# SCH_abi_2024-02-13.net
KiCad netlist of a schematic drawn in EasyEDA
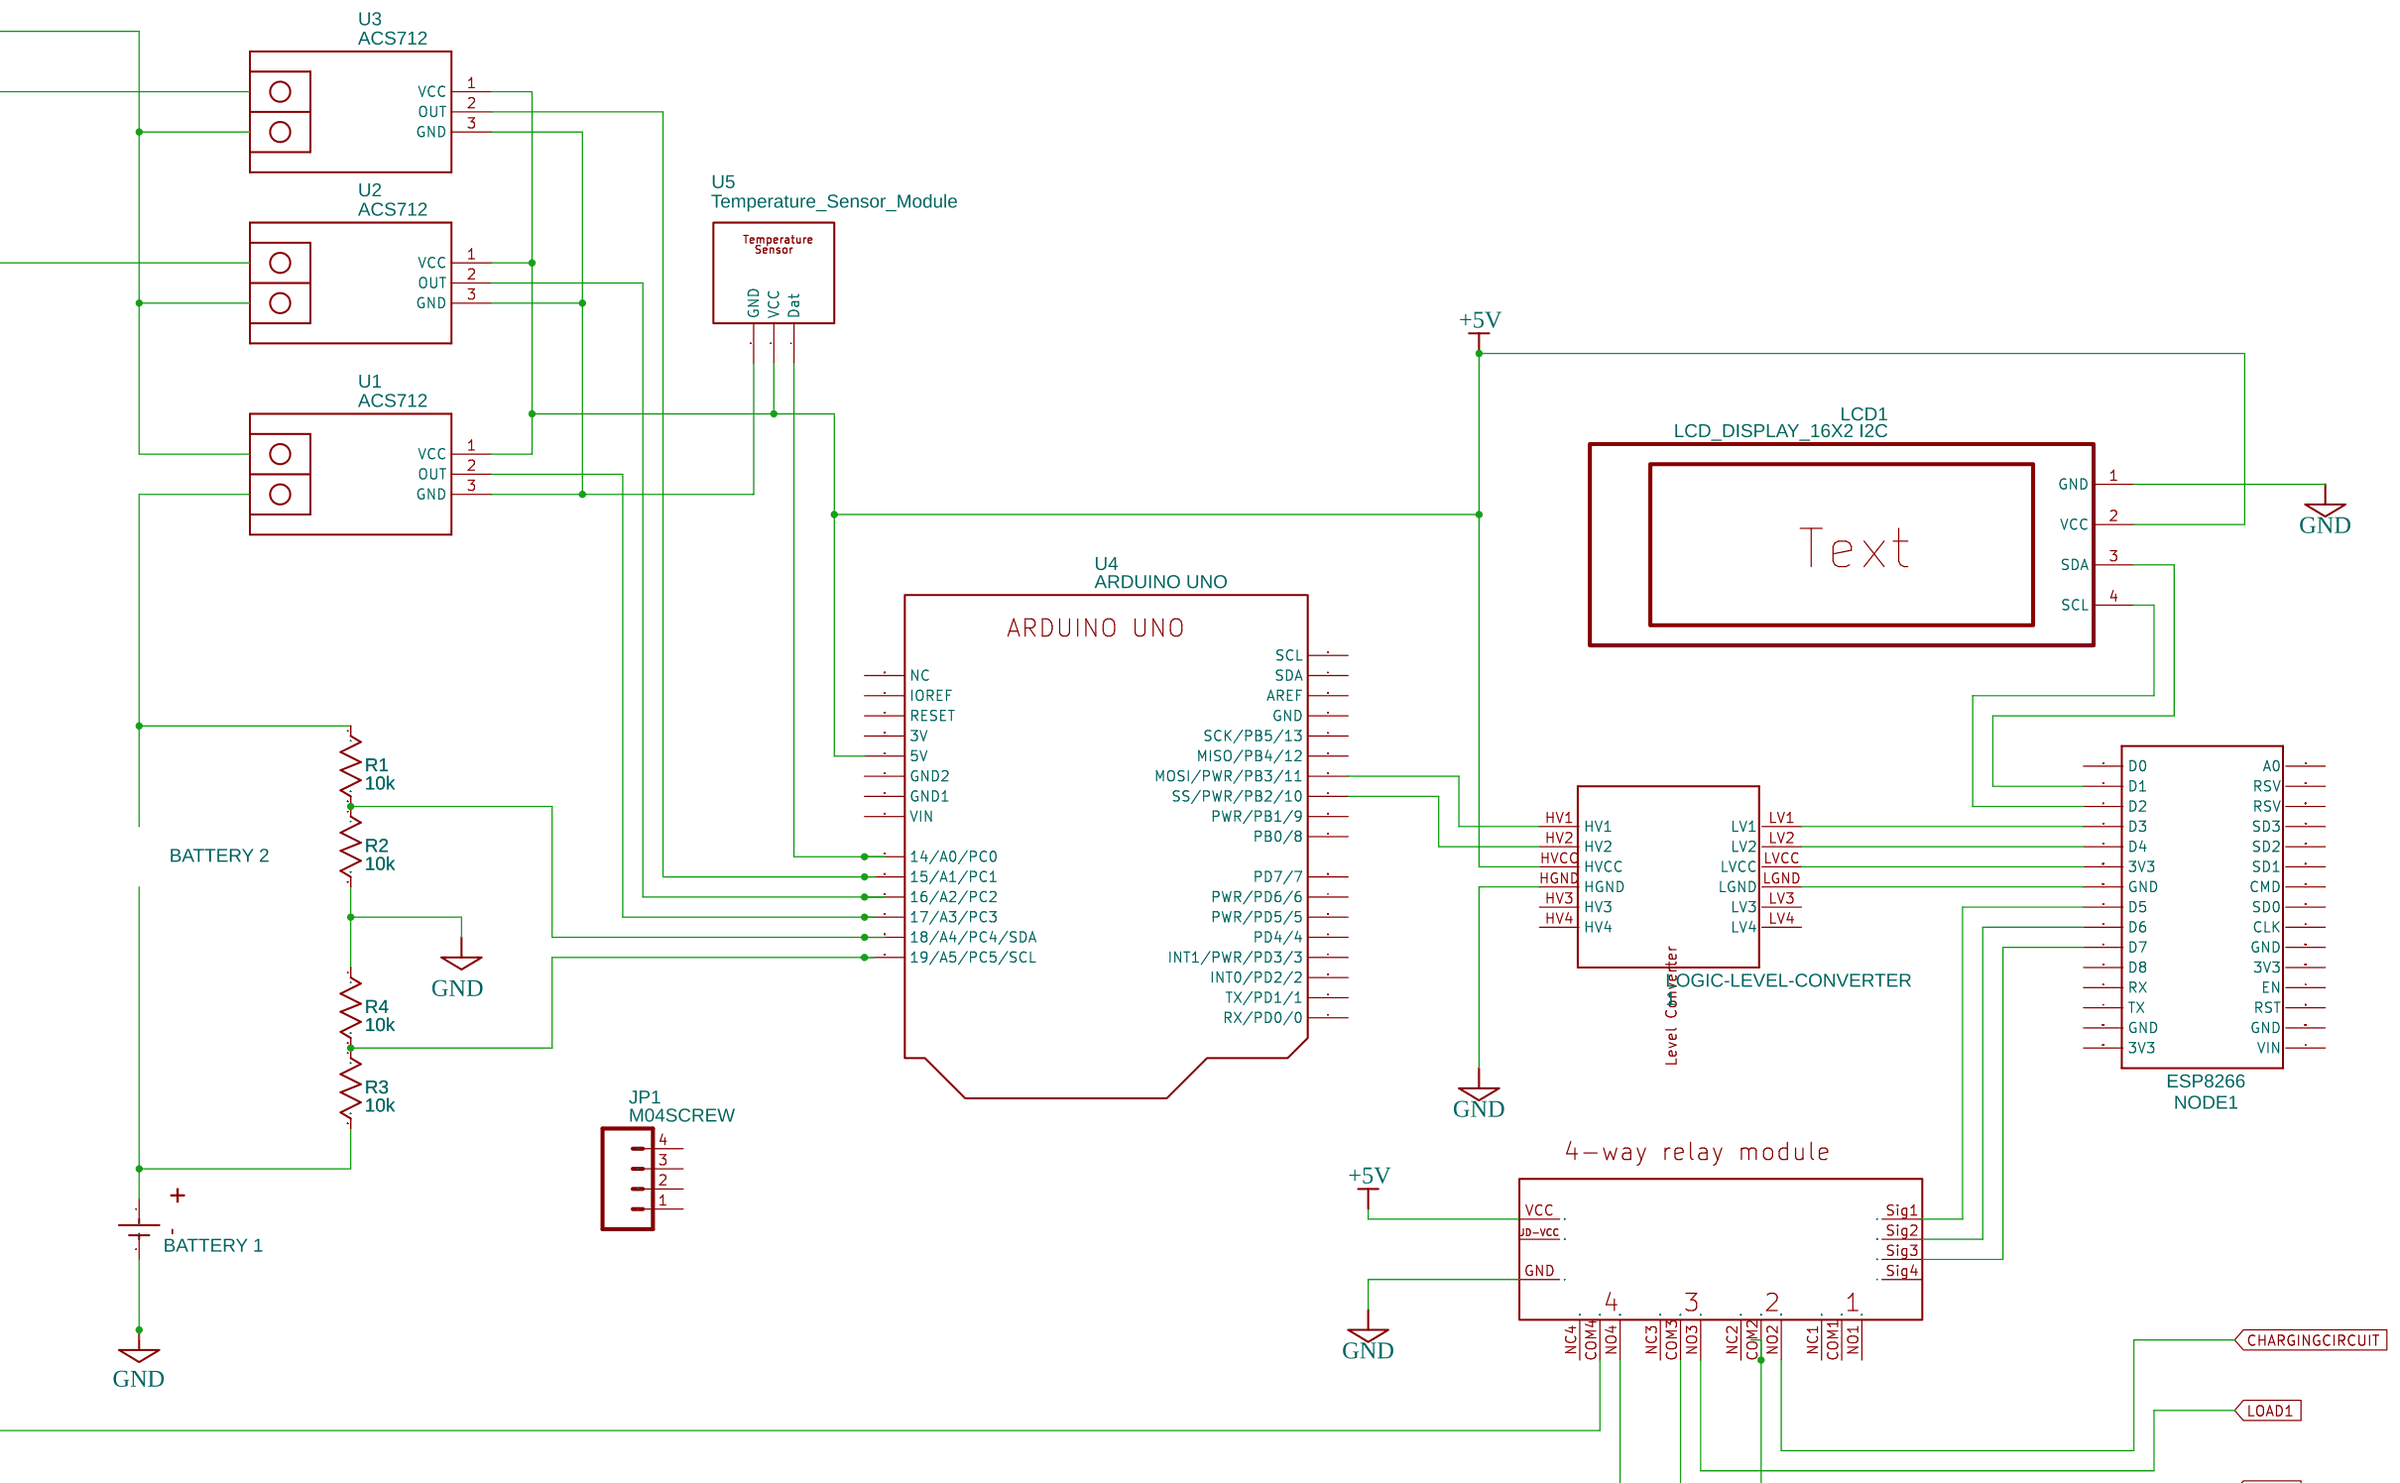
[diagram p0: schematic sheet]

(export (version "E")
  (design (tool "Eeschema 10.0.6"))
  (components
    (comp (ref "1") (value "LOGIC-LEVEL-CONVERTER") (libsource (lib "") (part "LOGIC-LEVEL-CONVERTER")))
    (comp (ref "G2") (value "BATTERY 1") (libsource (lib "") (part "BATTERY-1ELEMENT_RevE_Date15jun2010")))
    (comp (ref "JP1") (value "M04SCREW") (libsource (lib "") (part "M04SCREW")))
    (comp (ref "LCD1") (value "LCD_DISPLAY_16X2 I2C") (libsource (lib "") (part "LCD_DISPLAY_16X2 I2C")))
    (comp (ref "NODE1") (value "ESP8266") (libsource (lib "") (part "ESP8266 COPY")))
    (comp (ref "R1") (value "10k") (libsource (lib "") (part "R_0603_US")))
    (comp (ref "R2") (value "10k") (libsource (lib "") (part "R_0603_US")))
    (comp (ref "R3") (value "10k") (libsource (lib "") (part "R_0603_US")))
    (comp (ref "R4") (value "10k") (libsource (lib "") (part "R_0603_US")))
    (comp (ref "U1") (value "ACS712") (libsource (lib "") (part "CURRENT-SENSOR-ACS712")))
    (comp (ref "U2") (value "ACS712") (libsource (lib "") (part "CURRENT-SENSOR-ACS712")))
    (comp (ref "U3") (value "ACS712") (libsource (lib "") (part "CURRENT-SENSOR-ACS712")))
    (comp (ref "U4") (value "ARDUINO UNO") (libsource (lib "") (part "ARDUINO UNO")))
    (comp (ref "U5")
      (value "Temperature_Sensor_Module")
      (libsource (lib "") (part "DS18B20_Temperature_Sensor_Module"))
    )
    (comp (ref "U6") (value "4 way relay") (libsource (lib "") (part "4 way relay")))
  )
  (nets
    (net (code "1") (name "+5V") (class "Default")
      (node (ref "1") (pin "HVCC") (pinfunction "HVCC_HVCC") (pintype "bidirectional"))
      (node (ref "LCD1") (pin "2") (pinfunction "VCC_2") (pintype "passive"))
      (node (ref "U1") (pin "1") (pinfunction "VCC_1") (pintype "passive"))
      (node (ref "U2") (pin "1") (pinfunction "VCC_1") (pintype "passive"))
      (node (ref "U3") (pin "1") (pinfunction "VCC_1") (pintype "passive"))
      (node (ref "U4") (pin "28") (pinfunction "5V_28") (pintype "passive"))
      (node (ref "U5") (pin "2") (pinfunction "VCC_2") (pintype "unspecified"))
      (node (ref "U6") (pin "VCC") (pinfunction "6_VCC") (pintype "unspecified"))
    )
    (net (code "2") (name "CHARGINGCIRCUIT") (class "Default")
      (node (ref "U6") (pin "NO2") (pinfunction "8_NO2") (pintype "unspecified"))
    )
    (net (code "3") (name "GND") (class "Default")
      (node (ref "1") (pin "HGND") (pinfunction "HGND_HGND") (pintype "bidirectional"))
      (node (ref "G2") (pin "2") (pinfunction "Minus_2") (pintype "bidirectional"))
      (node (ref "LCD1") (pin "1") (pinfunction "GND_1") (pintype "passive"))
      (node (ref "R2") (pin "2") (pinfunction "2_2") (pintype "unspecified"))
      (node (ref "R4") (pin "1") (pinfunction "1_1") (pintype "unspecified"))
      (node (ref "U6") (pin "GND") (pinfunction "5_GND") (pintype "unspecified"))
    )
    (net (code "4") (name "LOAD1") (class "Default")
      (node (ref "U6") (pin "NO3") (pinfunction "8_NO3") (pintype "unspecified"))
    )
    (net (code "5") (name "LOAD2") (class "Default")
      (node (ref "U6") (pin "NO4") (pinfunction "8_NO4") (pintype "unspecified"))
    )
    (net (code "6") (name "Net-(1-PadLGND)") (class "Default")
      (node (ref "1") (pin "LGND") (pinfunction "LGND_LGND") (pintype "bidirectional"))
      (node (ref "NODE1") (pin "GND@2") (pinfunction "GND_GND@2") (pintype "bidirectional"))
    )
    (net (code "7") (name "Net-(1-PadLV1)") (class "Default")
      (node (ref "1") (pin "LV1") (pinfunction "LV1_LV1") (pintype "bidirectional"))
      (node (ref "NODE1") (pin "D3") (pinfunction "D3_D3") (pintype "bidirectional"))
    )
    (net (code "8") (name "Net-(1-PadLV2)") (class "Default")
      (node (ref "1") (pin "LV2") (pinfunction "LV2_LV2") (pintype "bidirectional"))
      (node (ref "NODE1") (pin "D4") (pinfunction "D4_D4") (pintype "bidirectional"))
    )
    (net (code "9") (name "Net-(1-PadLVCC)") (class "Default")
      (node (ref "1") (pin "LVCC") (pinfunction "LVCC_LVCC") (pintype "bidirectional"))
      (node (ref "NODE1") (pin "3V3@2") (pinfunction "3V3_3V3@2") (pintype "bidirectional"))
    )
    (net (code "10") (name "Net-(G2-Plus)") (class "Default")
      (node (ref "G2") (pin "1") (pinfunction "Plus_1") (pintype "bidirectional"))
      (node (ref "R3") (pin "2") (pinfunction "2_2") (pintype "unspecified"))
    )
    (net (code "11") (name "Net-(LCD1-SCL)") (class "Default")
      (node (ref "LCD1") (pin "4") (pinfunction "SCL_4") (pintype "passive"))
      (node (ref "NODE1") (pin "D2") (pinfunction "D2_D2") (pintype "bidirectional"))
    )
    (net (code "12") (name "Net-(LCD1-SDA)") (class "Default")
      (node (ref "LCD1") (pin "3") (pinfunction "SDA_3") (pintype "passive"))
      (node (ref "NODE1") (pin "D1") (pinfunction "D1_D1") (pintype "bidirectional"))
    )
    (net (code "13") (name "Net-(U1-GND)") (class "Default")
      (node (ref "U1") (pin "3") (pinfunction "GND_3") (pintype "passive"))
      (node (ref "U2") (pin "3") (pinfunction "GND_3") (pintype "passive"))
      (node (ref "U3") (pin "3") (pinfunction "GND_3") (pintype "passive"))
      (node (ref "U5") (pin "3") (pinfunction "GND_3") (pintype "unspecified"))
    )
    (net (code "14") (name "Net-(U1-OUT)") (class "Default")
      (node (ref "U1") (pin "2") (pinfunction "OUT_2") (pintype "output"))
      (node (ref "U4") (pin "21") (pinfunction "17/A3/PC3_21") (pintype "unspecified"))
    )
    (net (code "15") (name "Net-(U2-OUT)") (class "Default")
      (node (ref "U2") (pin "2") (pinfunction "OUT_2") (pintype "output"))
      (node (ref "U4") (pin "22") (pinfunction "16/A2/PC2_22") (pintype "unspecified"))
    )
    (net (code "16") (name "Net-(U3-OUT)") (class "Default")
      (node (ref "U3") (pin "2") (pinfunction "OUT_2") (pintype "output"))
      (node (ref "U4") (pin "23") (pinfunction "15/A1/PC1_23") (pintype "unspecified"))
    )
    (net (code "17") (name "Net-(U4-14{slash}A0{slash}PC0)") (class "Default")
      (node (ref "U4") (pin "24") (pinfunction "14/A0/PC0_24") (pintype "unspecified"))
      (node (ref "U5") (pin "1") (pinfunction "Dat_1") (pintype "unspecified"))
    )
    (net (code "18") (name "Net-(U4-18{slash}A4{slash}PC4{slash}SDA)") (class "Default")
      (node (ref "R1") (pin "2") (pinfunction "2_2") (pintype "unspecified"))
      (node (ref "R2") (pin "1") (pinfunction "1_1") (pintype "unspecified"))
      (node (ref "U4") (pin "20") (pinfunction "18/A4/PC4/SDA_20") (pintype "unspecified"))
    )
    (net (code "19") (name "Net-(U4-19{slash}A5{slash}PC5{slash}SCL)") (class "Default")
      (node (ref "R3") (pin "1") (pinfunction "1_1") (pintype "unspecified"))
      (node (ref "R4") (pin "2") (pinfunction "2_2") (pintype "unspecified"))
      (node (ref "U4") (pin "19") (pinfunction "19/A5/PC5/SCL_19") (pintype "unspecified"))
    )
    (net (code "20") (name "Net-(U4-MOSI{slash}PWR{slash}PB3{slash}11)") (class "Default")
      (node (ref "1") (pin "HV1") (pinfunction "HV1_HV1") (pintype "bidirectional"))
      (node (ref "U4") (pin "12") (pinfunction "MOSI/PWR/PB3/11_12") (pintype "unspecified"))
    )
    (net (code "21") (name "Net-(U4-SS{slash}PWR{slash}PB2{slash}10)") (class "Default")
      (node (ref "1") (pin "HV2") (pinfunction "HV2_HV2") (pintype "bidirectional"))
      (node (ref "U4") (pin "11") (pinfunction "SS/PWR/PB2/10_11") (pintype "unspecified"))
    )
    (net (code "22") (name "Net-(U6-1)") (class "Default")
      (node (ref "NODE1") (pin "D5") (pinfunction "D5_D5") (pintype "bidirectional"))
      (node (ref "U6") (pin "Sig1") (pinfunction "1_Sig1") (pintype "unspecified"))
    )
    (net (code "23") (name "Net-(U6-2)") (class "Default")
      (node (ref "NODE1") (pin "D6") (pinfunction "D6_D6") (pintype "bidirectional"))
      (node (ref "U6") (pin "Sig2") (pinfunction "2_Sig2") (pintype "unspecified"))
    )
    (net (code "24") (name "Net-(U6-3)") (class "Default")
      (node (ref "NODE1") (pin "D7") (pinfunction "D7_D7") (pintype "bidirectional"))
      (node (ref "U6") (pin "Sig3") (pinfunction "3_Sig3") (pintype "unspecified"))
    )
    (net (code "25") (name "unconnected-(1-PadHV3)") (class "Default")
      (node (ref "1") (pin "HV3") (pinfunction "HV3_HV3") (pintype "bidirectional"))
    )
    (net (code "26") (name "unconnected-(1-PadHV4)") (class "Default")
      (node (ref "1") (pin "HV4") (pinfunction "HV4_HV4") (pintype "bidirectional"))
    )
    (net (code "27") (name "unconnected-(1-PadLV3)") (class "Default")
      (node (ref "1") (pin "LV3") (pinfunction "LV3_LV3") (pintype "bidirectional"))
    )
    (net (code "28") (name "unconnected-(1-PadLV4)") (class "Default")
      (node (ref "1") (pin "LV4") (pinfunction "LV4_LV4") (pintype "bidirectional"))
    )
    (net (code "29") (name "unconnected-(JP1-Pad1)") (class "Default")
      (node (ref "JP1") (pin "1") (pinfunction "1_1") (pintype "unspecified"))
    )
    (net (code "30") (name "unconnected-(JP1-Pad2)") (class "Default")
      (node (ref "JP1") (pin "2") (pinfunction "2_2") (pintype "unspecified"))
    )
    (net (code "31") (name "unconnected-(JP1-Pad3)") (class "Default")
      (node (ref "JP1") (pin "3") (pinfunction "3_3") (pintype "unspecified"))
    )
    (net (code "32") (name "unconnected-(JP1-Pad4)") (class "Default")
      (node (ref "JP1") (pin "4") (pinfunction "4_4") (pintype "unspecified"))
    )
    (net (code "33") (name "unconnected-(NODE1-3V3-Pad3V3@1)") (class "Default")
      (node (ref "NODE1") (pin "3V3@1") (pinfunction "3V3_3V3@1") (pintype "bidirectional"))
    )
    (net (code "34") (name "unconnected-(NODE1-3V3-Pad3V3@3)") (class "Default")
      (node (ref "NODE1") (pin "3V3@3") (pinfunction "3V3_3V3@3") (pintype "bidirectional"))
    )
    (net (code "35") (name "unconnected-(NODE1-GND-PadGND@1)") (class "Default")
      (node (ref "NODE1") (pin "GND@1") (pinfunction "GND_GND@1") (pintype "bidirectional"))
    )
    (net (code "36") (name "unconnected-(NODE1-GND-PadGND@3)") (class "Default")
      (node (ref "NODE1") (pin "GND@3") (pinfunction "GND_GND@3") (pintype "bidirectional"))
    )
    (net (code "37") (name "unconnected-(NODE1-GND-PadGND@4)") (class "Default")
      (node (ref "NODE1") (pin "GND@4") (pinfunction "GND_GND@4") (pintype "bidirectional"))
    )
    (net (code "38") (name "unconnected-(NODE1-PadA0)") (class "Default")
      (node (ref "NODE1") (pin "A0") (pinfunction "A0_A0") (pintype "bidirectional"))
    )
    (net (code "39") (name "unconnected-(NODE1-PadCLK)") (class "Default")
      (node (ref "NODE1") (pin "CLK") (pinfunction "CLK_CLK") (pintype "bidirectional"))
    )
    (net (code "40") (name "unconnected-(NODE1-PadCMD)") (class "Default")
      (node (ref "NODE1") (pin "CMD") (pinfunction "CMD_CMD") (pintype "bidirectional"))
    )
    (net (code "41") (name "unconnected-(NODE1-PadD0)") (class "Default")
      (node (ref "NODE1") (pin "D0") (pinfunction "D0_D0") (pintype "bidirectional"))
    )
    (net (code "42") (name "unconnected-(NODE1-PadD8)") (class "Default")
      (node (ref "NODE1") (pin "D8") (pinfunction "D8_D8") (pintype "bidirectional"))
    )
    (net (code "43") (name "unconnected-(NODE1-PadEN)") (class "Default")
      (node (ref "NODE1") (pin "EN") (pinfunction "EN_EN") (pintype "bidirectional"))
    )
    (net (code "44") (name "unconnected-(NODE1-PadRST)") (class "Default")
      (node (ref "NODE1") (pin "RST") (pinfunction "RST_RST") (pintype "bidirectional"))
    )
    (net (code "45") (name "unconnected-(NODE1-PadRX)") (class "Default")
      (node (ref "NODE1") (pin "RX") (pinfunction "RX_RX") (pintype "bidirectional"))
    )
    (net (code "46") (name "unconnected-(NODE1-PadSD1)") (class "Default")
      (node (ref "NODE1") (pin "SD1") (pinfunction "SD1_SD1") (pintype "bidirectional"))
    )
    (net (code "47") (name "unconnected-(NODE1-PadSD2)") (class "Default")
      (node (ref "NODE1") (pin "SD2") (pinfunction "SD2_SD2") (pintype "bidirectional"))
    )
    (net (code "48") (name "unconnected-(NODE1-PadSD3)") (class "Default")
      (node (ref "NODE1") (pin "SD3") (pinfunction "SD3_SD3") (pintype "bidirectional"))
    )
    (net (code "49") (name "unconnected-(NODE1-PadTX)") (class "Default")
      (node (ref "NODE1") (pin "TX") (pinfunction "TX_TX") (pintype "bidirectional"))
    )
    (net (code "50") (name "unconnected-(NODE1-PadVIN)") (class "Default")
      (node (ref "NODE1") (pin "VIN") (pinfunction "VIN_VIN") (pintype "bidirectional"))
    )
    (net (code "51") (name "unconnected-(NODE1-RSV-PadRSV1)") (class "Default")
      (node (ref "NODE1") (pin "RSV1") (pinfunction "RSV_RSV1") (pintype "bidirectional"))
    )
    (net (code "52") (name "unconnected-(NODE1-RSV-PadRSV2)") (class "Default")
      (node (ref "NODE1") (pin "RSV2") (pinfunction "RSV_RSV2") (pintype "bidirectional"))
    )
    (net (code "53") (name "unconnected-(NODE1-SD0-PadSDO)") (class "Default")
      (node (ref "NODE1") (pin "SDO") (pinfunction "SD0_SDO") (pintype "bidirectional"))
    )
    (net (code "54") (name "unconnected-(R1-Pad1)") (class "Default")
      (node (ref "R1") (pin "1") (pinfunction "1_1") (pintype "unspecified"))
    )
    (net (code "55") (name "unconnected-(U4-3V-Pad29)") (class "Default")
      (node (ref "U4") (pin "29") (pinfunction "3V_29") (pintype "passive"))
    )
    (net (code "56") (name "unconnected-(U4-AREF-Pad16)") (class "Default")
      (node (ref "U4") (pin "16") (pinfunction "AREF_16") (pintype "unspecified"))
    )
    (net (code "57") (name "unconnected-(U4-GND-Pad15)") (class "Default")
      (node (ref "U4") (pin "15") (pinfunction "GND_15") (pintype "passive"))
    )
    (net (code "58") (name "unconnected-(U4-GND1-Pad26)") (class "Default")
      (node (ref "U4") (pin "26") (pinfunction "GND1_26") (pintype "passive"))
    )
    (net (code "59") (name "unconnected-(U4-GND2-Pad27)") (class "Default")
      (node (ref "U4") (pin "27") (pinfunction "GND2_27") (pintype "passive"))
    )
    (net (code "60") (name "unconnected-(U4-INT0{slash}PD2{slash}2-Pad3)") (class "Default")
      (node (ref "U4") (pin "3") (pinfunction "INT0/PD2/2_3") (pintype "unspecified"))
    )
    (net (code "61") (name "unconnected-(U4-INT1{slash}PWR{slash}PD3{slash}3-Pad4)") (class "Default")
      (node (ref "U4") (pin "4") (pinfunction "INT1/PWR/PD3/3_4") (pintype "unspecified"))
    )
    (net (code "62") (name "unconnected-(U4-IOREF-Pad31)") (class "Default")
      (node (ref "U4") (pin "31") (pinfunction "IOREF_31") (pintype "unspecified"))
    )
    (net (code "63") (name "unconnected-(U4-MISO{slash}PB4{slash}12-Pad13)") (class "Default")
      (node (ref "U4") (pin "13") (pinfunction "MISO/PB4/12_13") (pintype "unspecified"))
    )
    (net (code "64") (name "unconnected-(U4-NC-Pad32)") (class "Default")
      (node (ref "U4") (pin "32") (pinfunction "NC_32") (pintype "unspecified"))
    )
    (net (code "65") (name "unconnected-(U4-PB0{slash}8-Pad9)") (class "Default")
      (node (ref "U4") (pin "9") (pinfunction "PB0/8_9") (pintype "unspecified"))
    )
    (net (code "66") (name "unconnected-(U4-PD4{slash}4-Pad5)") (class "Default")
      (node (ref "U4") (pin "5") (pinfunction "PD4/4_5") (pintype "unspecified"))
    )
    (net (code "67") (name "unconnected-(U4-PD7{slash}7-Pad8)") (class "Default")
      (node (ref "U4") (pin "8") (pinfunction "PD7/7_8") (pintype "unspecified"))
    )
    (net (code "68") (name "unconnected-(U4-PWR{slash}PB1{slash}9-Pad10)") (class "Default")
      (node (ref "U4") (pin "10") (pinfunction "PWR/PB1/9_10") (pintype "unspecified"))
    )
    (net (code "69") (name "unconnected-(U4-PWR{slash}PD5{slash}5-Pad6)") (class "Default")
      (node (ref "U4") (pin "6") (pinfunction "PWR/PD5/5_6") (pintype "unspecified"))
    )
    (net (code "70") (name "unconnected-(U4-PWR{slash}PD6{slash}6-Pad7)") (class "Default")
      (node (ref "U4") (pin "7") (pinfunction "PWR/PD6/6_7") (pintype "unspecified"))
    )
    (net (code "71") (name "unconnected-(U4-RESET-Pad30)") (class "Default")
      (node (ref "U4") (pin "30") (pinfunction "RESET_30") (pintype "unspecified"))
    )
    (net (code "72") (name "unconnected-(U4-RX{slash}PD0{slash}0-Pad1)") (class "Default")
      (node (ref "U4") (pin "1") (pinfunction "RX/PD0/0_1") (pintype "unspecified"))
    )
    (net (code "73") (name "unconnected-(U4-SCK{slash}PB5{slash}13-Pad14)") (class "Default")
      (node (ref "U4") (pin "14") (pinfunction "SCK/PB5/13_14") (pintype "unspecified"))
    )
    (net (code "74") (name "unconnected-(U4-SCL-Pad18)") (class "Default")
      (node (ref "U4") (pin "18") (pinfunction "SCL_18") (pintype "unspecified"))
    )
    (net (code "75") (name "unconnected-(U4-SDA-Pad17)") (class "Default")
      (node (ref "U4") (pin "17") (pinfunction "SDA_17") (pintype "unspecified"))
    )
    (net (code "76") (name "unconnected-(U4-TX{slash}PD1{slash}1-Pad2)") (class "Default")
      (node (ref "U4") (pin "2") (pinfunction "TX/PD1/1_2") (pintype "unspecified"))
    )
    (net (code "77") (name "unconnected-(U4-VIN-Pad25)") (class "Default")
      (node (ref "U4") (pin "25") (pinfunction "VIN_25") (pintype "passive"))
    )
    (net (code "78") (name "unconnected-(U6-4-PadSig4)") (class "Default")
      (node (ref "U6") (pin "Sig4") (pinfunction "4_Sig4") (pintype "unspecified"))
    )
    (net (code "79") (name "unconnected-(U6-6-PadJD-VCC)") (class "Default")
      (node (ref "U6") (pin "JD-VCC") (pinfunction "6_JD-VCC") (pintype "unspecified"))
    )
    (net (code "80") (name "unconnected-(U6-8-PadCOM1)") (class "Default")
      (node (ref "U6") (pin "COM1") (pinfunction "8_COM1") (pintype "unspecified"))
    )
    (net (code "81") (name "unconnected-(U6-8-PadCOM2)") (class "Default")
      (node (ref "U6") (pin "COM2") (pinfunction "8_COM2") (pintype "unspecified"))
    )
    (net (code "82") (name "unconnected-(U6-8-PadCOM3)") (class "Default")
      (node (ref "U6") (pin "COM3") (pinfunction "8_COM3") (pintype "unspecified"))
    )
    (net (code "83") (name "unconnected-(U6-8-PadCOM4)") (class "Default")
      (node (ref "U6") (pin "COM4") (pinfunction "8_COM4") (pintype "unspecified"))
    )
    (net (code "84") (name "unconnected-(U6-8-PadNC1)") (class "Default")
      (node (ref "U6") (pin "NC1") (pinfunction "8_NC1") (pintype "unspecified"))
    )
    (net (code "85") (name "unconnected-(U6-8-PadNC2)") (class "Default")
      (node (ref "U6") (pin "NC2") (pinfunction "8_NC2") (pintype "unspecified"))
    )
    (net (code "86") (name "unconnected-(U6-8-PadNC3)") (class "Default")
      (node (ref "U6") (pin "NC3") (pinfunction "8_NC3") (pintype "unspecified"))
    )
    (net (code "87") (name "unconnected-(U6-8-PadNC4)") (class "Default")
      (node (ref "U6") (pin "NC4") (pinfunction "8_NC4") (pintype "unspecified"))
    )
    (net (code "88") (name "unconnected-(U6-8-PadNO1)") (class "Default")
      (node (ref "U6") (pin "NO1") (pinfunction "8_NO1") (pintype "unspecified"))
    )
  )
)
